# 01_Main.net
KiCad netlist of a schematic drawn in Altium Designer
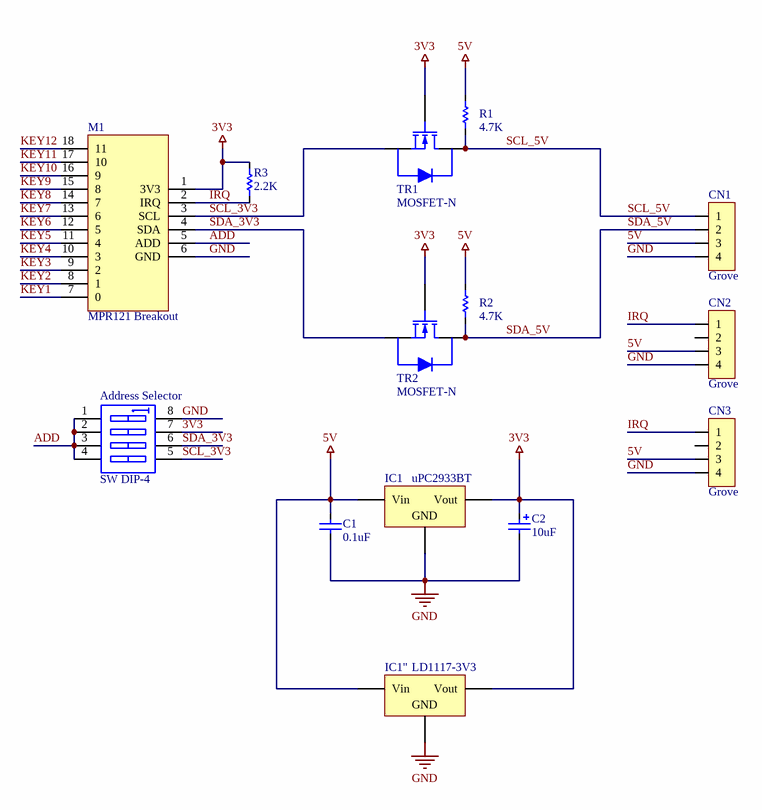
[diagram p0: 01.Main.SchDoc]

(export (version "E")
  (design (tool "Eeschema 10.0.6"))
  (components
    (comp (ref "Address Selector")
      (value "SW DIP-4")
      (footprint "DIP-8")
      (description "DIP Switch, 4 Position, SPST")
      (fields (field (name "PUBLISHER") "Altium Limited"))
      (libsource (lib "Miscellaneous Devices") (part "SW DIP-4"))
    )
    (comp (ref "C1")
      (value "0.1uF")
      (footprint "Cap NP 5mm")
      (libsource (lib "MainnoLab library") (part "Capacitor Non-Polar"))
    )
    (comp (ref "C2")
      (value "10uF")
      (footprint "Cap 5mm")
      (libsource (lib "MainnoLab library") (part "Capacitor Polar"))
    )
    (comp (ref "CN1")
      (value "Grove")
      (footprint "Grove-4P-180D")
      (libsource (lib "MainnoLab library") (part "Connector 1X4"))
    )
    (comp (ref "CN2")
      (value "Grove")
      (footprint "Grove-4P-180D")
      (libsource (lib "MainnoLab library") (part "Connector 1X4"))
    )
    (comp (ref "CN3")
      (value "Grove")
      (footprint "Grove-4P-180D")
      (libsource (lib "MainnoLab library") (part "Connector 1X4"))
    )
    (comp (ref "IC1")
      (value "uPC2933BT")
      (footprint "D2PAK_M")
      (description "Voltage Regulator")
      (fields (field (name "PUBLISHER") "Altium Limited"))
      (libsource (lib "MainnoLab library") (part "Volt Reg_1"))
    )
    (comp (ref "IC1\"")
      (value "LD1117-3V3")
      (footprint "sot223_M")
      (description "Voltage Regulator")
      (fields (field (name "PUBLISHER") "Altium Limited"))
      (libsource (lib "MainnoLab library") (part "Volt Reg_1"))
    )
    (comp (ref "M1")
      (value "MPR121 Breakout")
      (footprint "MPR121 Breakout")
      (libsource (lib "MainnoLab library") (part "MPR121 Breakout"))
    )
    (comp (ref "R1")
      (value "4.7K")
      (footprint "Res 1/4W")
      (libsource (lib "MainnoLab library") (part "Resistor"))
    )
    (comp (ref "R2")
      (value "4.7K")
      (footprint "Res 1/4W")
      (libsource (lib "MainnoLab library") (part "Resistor"))
    )
    (comp (ref "R3")
      (value "2.2K")
      (footprint "0805")
      (libsource (lib "MainnoLab library") (part "Resistor"))
    )
    (comp (ref "TR1")
      (value "MOSFET-N")
      (footprint "to-92")
      (description "N-Channel MOSFET")
      (fields (field (name "PUBLISHER") "Altium Limited"))
      (libsource (lib "MainnoLab library") (part "MOSFET-N"))
    )
    (comp (ref "TR2")
      (value "MOSFET-N")
      (footprint "to-92")
      (description "N-Channel MOSFET")
      (fields (field (name "PUBLISHER") "Altium Limited"))
      (libsource (lib "MainnoLab library") (part "MOSFET-N"))
    )
  )
  (nets
    (net (code "1") (name "/ADD") (class "Default")
      (node (ref "Address Selector") (pin "1") (pinfunction "A1_1") (pintype "passive"))
      (node (ref "Address Selector") (pin "2") (pinfunction "A2_2") (pintype "passive"))
      (node (ref "Address Selector") (pin "3") (pinfunction "A3_3") (pintype "passive"))
      (node (ref "Address Selector") (pin "4") (pinfunction "A4_4") (pintype "passive"))
      (node (ref "M1") (pin "5") (pinfunction "ADD_5") (pintype "passive"))
    )
    (net (code "2") (name "/IRQ") (class "Default")
      (node (ref "CN2") (pin "1") (pinfunction "1_1") (pintype "passive"))
      (node (ref "CN3") (pin "1") (pinfunction "1_1") (pintype "passive"))
      (node (ref "M1") (pin "2") (pinfunction "IRQ_2") (pintype "passive"))
      (node (ref "R3") (pin "1") (pinfunction "1_1") (pintype "passive"))
    )
    (net (code "3") (name "/KEY1") (class "Default")
      (node (ref "M1") (pin "7") (pinfunction "0_7") (pintype "passive"))
    )
    (net (code "4") (name "/KEY2") (class "Default")
      (node (ref "M1") (pin "8") (pinfunction "1_8") (pintype "passive"))
    )
    (net (code "5") (name "/KEY3") (class "Default")
      (node (ref "M1") (pin "9") (pinfunction "2_9") (pintype "passive"))
    )
    (net (code "6") (name "/KEY4") (class "Default")
      (node (ref "M1") (pin "10") (pinfunction "3_10") (pintype "passive"))
    )
    (net (code "7") (name "/KEY5") (class "Default")
      (node (ref "M1") (pin "11") (pinfunction "4_11") (pintype "passive"))
    )
    (net (code "8") (name "/KEY6") (class "Default")
      (node (ref "M1") (pin "12") (pinfunction "5_12") (pintype "passive"))
    )
    (net (code "9") (name "/KEY7") (class "Default")
      (node (ref "M1") (pin "13") (pinfunction "6_13") (pintype "passive"))
    )
    (net (code "10") (name "/KEY8") (class "Default")
      (node (ref "M1") (pin "14") (pinfunction "7_14") (pintype "passive"))
    )
    (net (code "11") (name "/KEY9") (class "Default")
      (node (ref "M1") (pin "15") (pinfunction "8_15") (pintype "passive"))
    )
    (net (code "12") (name "/KEY10") (class "Default")
      (node (ref "M1") (pin "16") (pinfunction "9_16") (pintype "passive"))
    )
    (net (code "13") (name "/KEY11") (class "Default")
      (node (ref "M1") (pin "17") (pinfunction "10_17") (pintype "passive"))
    )
    (net (code "14") (name "/KEY12") (class "Default")
      (node (ref "M1") (pin "18") (pinfunction "11_18") (pintype "passive"))
    )
    (net (code "15") (name "/SCL_3V3") (class "Default")
      (node (ref "Address Selector") (pin "5") (pinfunction "B4_5") (pintype "passive"))
      (node (ref "M1") (pin "3") (pinfunction "SCL_3") (pintype "passive"))
      (node (ref "TR1") (pin "1") (pinfunction "S_1") (pintype "passive"))
    )
    (net (code "16") (name "/SCL_5V") (class "Default")
      (node (ref "CN1") (pin "1") (pinfunction "1_1") (pintype "passive"))
      (node (ref "R1") (pin "1") (pinfunction "1_1") (pintype "passive"))
      (node (ref "TR1") (pin "3") (pinfunction "D_3") (pintype "passive"))
    )
    (net (code "17") (name "/SDA_3V3") (class "Default")
      (node (ref "Address Selector") (pin "6") (pinfunction "B3_6") (pintype "passive"))
      (node (ref "M1") (pin "4") (pinfunction "SDA_4") (pintype "passive"))
      (node (ref "TR2") (pin "1") (pinfunction "S_1") (pintype "passive"))
    )
    (net (code "18") (name "/SDA_5V") (class "Default")
      (node (ref "CN1") (pin "2") (pinfunction "2_2") (pintype "passive"))
      (node (ref "R2") (pin "1") (pinfunction "1_1") (pintype "passive"))
      (node (ref "TR2") (pin "3") (pinfunction "D_3") (pintype "passive"))
    )
    (net (code "19") (name "3V3") (class "Default")
      (node (ref "Address Selector") (pin "7") (pinfunction "B2_7") (pintype "passive"))
      (node (ref "C2") (pin "1") (pinfunction "1_1") (pintype "passive"))
      (node (ref "IC1") (pin "Vout") (pinfunction "Vout_Vout") (pintype "passive"))
      (node (ref "IC1\"") (pin "Vout") (pinfunction "Vout_Vout") (pintype "passive"))
      (node (ref "M1") (pin "1") (pinfunction "3V3_1") (pintype "passive"))
      (node (ref "R3") (pin "2") (pinfunction "2_2") (pintype "passive"))
      (node (ref "TR1") (pin "2") (pinfunction "G_2") (pintype "passive"))
      (node (ref "TR2") (pin "2") (pinfunction "G_2") (pintype "passive"))
    )
    (net (code "20") (name "5V") (class "Default")
      (node (ref "C1") (pin "2") (pinfunction "2_2") (pintype "passive"))
      (node (ref "CN1") (pin "3") (pinfunction "3_3") (pintype "passive"))
      (node (ref "CN2") (pin "3") (pinfunction "3_3") (pintype "passive"))
      (node (ref "CN3") (pin "3") (pinfunction "3_3") (pintype "passive"))
      (node (ref "IC1") (pin "Vin") (pinfunction "Vin_Vin") (pintype "passive"))
      (node (ref "IC1\"") (pin "Vin") (pinfunction "Vin_Vin") (pintype "passive"))
      (node (ref "R1") (pin "2") (pinfunction "2_2") (pintype "passive"))
      (node (ref "R2") (pin "2") (pinfunction "2_2") (pintype "passive"))
    )
    (net (code "21") (name "GND") (class "Default")
      (node (ref "Address Selector") (pin "8") (pinfunction "B1_8") (pintype "passive"))
      (node (ref "C1") (pin "1") (pinfunction "1_1") (pintype "passive"))
      (node (ref "C2") (pin "2") (pinfunction "2_2") (pintype "passive"))
      (node (ref "CN1") (pin "4") (pinfunction "4_4") (pintype "passive"))
      (node (ref "CN2") (pin "4") (pinfunction "4_4") (pintype "passive"))
      (node (ref "CN3") (pin "4") (pinfunction "4_4") (pintype "passive"))
      (node (ref "IC1") (pin "GND") (pinfunction "GND_GND") (pintype "passive"))
      (node (ref "IC1\"") (pin "GND") (pinfunction "GND_GND") (pintype "passive"))
      (node (ref "M1") (pin "6") (pinfunction "GND_6") (pintype "passive"))
    )
    (net (code "22") (name "unconnected-(CN2-Pad2)") (class "Default")
      (node (ref "CN2") (pin "2") (pinfunction "2_2") (pintype "passive"))
    )
    (net (code "23") (name "unconnected-(CN3-Pad2)") (class "Default")
      (node (ref "CN3") (pin "2") (pinfunction "2_2") (pintype "passive"))
    )
  )
)
